# IsoPowerSupply.net
KiCad netlist of a schematic drawn in Altium Designer
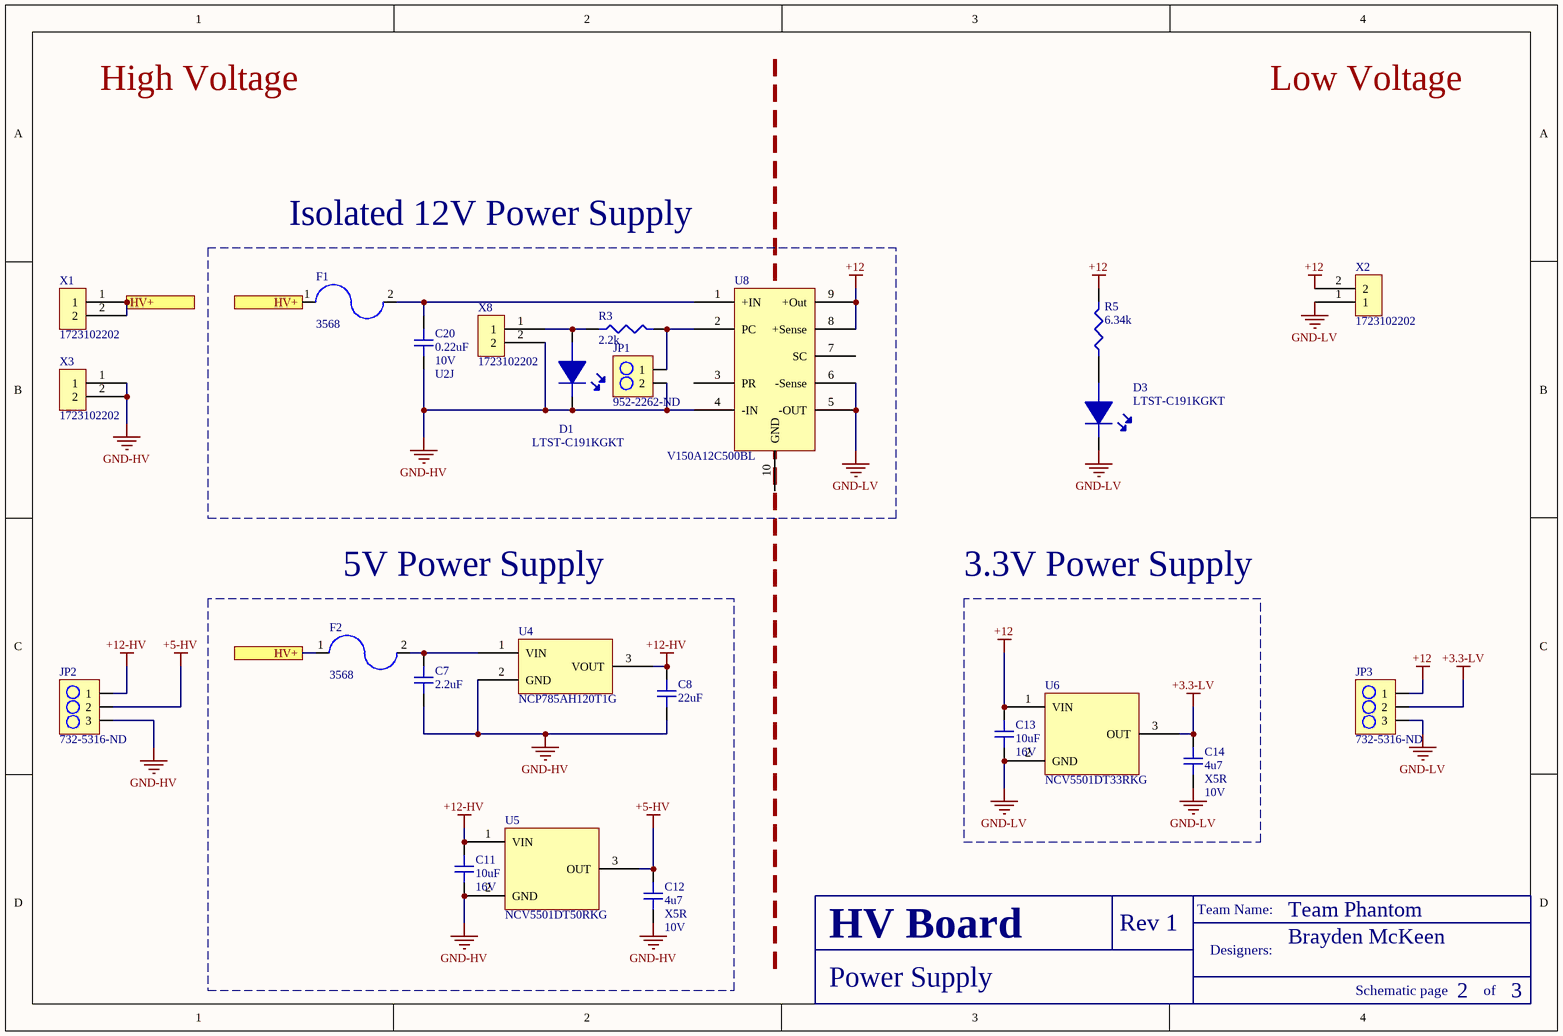
[diagram p0: IsoPowerSupply.SchDoc]

(export (version "E")
  (design (tool "Eeschema 10.0.6"))
  (components
    (comp (ref "C7")
      (value "2.2uF")
      (footprint "Cap-2.2u- ECW-FD2W225J4")
      (description "CAP FILM 2.2UF 5% 450VDC RADIAL")
      (fields
        (field (name "MANUFACTURER") "Panasonic")
        (field (name "MANUFACURER PART NUMBER") "ECW-FD2W225J4")
      )
      (libsource (lib "PHANTOM_LIBRARY") (part "ECW-FD2W225J4"))
    )
    (comp (ref "C8")
      (value "22uF")
      (footprint "C1206")
      (description "CAP CER 22UF 16V X7R 1210")
      (fields
        (field (name "MANUFACTURER") "Murata")
        (field (name "MANUFACTURER PART NUMBER") "GCM31CR71A226KE02L")
      )
      (libsource (lib "PHANTOM_LIBRARY") (part "GCM32ER71C226KE19L"))
    )
    (comp (ref "C11")
      (value "10uF")
      (footprint "PHANTOM_FOOTPRINTS:C0805")
      (description "CAP CER 10UF 16V X7R 0805")
      (fields
        (field (name "MANUFACTURER") "Samsung")
        (field (name "TOLERANCE") "10%")
        (field (name "VOLTAGE RATING") "16V")
      )
      (libsource (lib "PHANTOM_LIBRARY") (part "CL21B106KOQNNNG"))
    )
    (comp (ref "C12")
      (value "4u7")
      (footprint "C0805")
      (fields
        (field (name "MANUFACTURER") "Murata")
        (field (name "MANUFACTURER PART NUMBER") "GRM219R61A475KE34D")
        (field (name "TOLERANCE") "10%")
        (field (name "DIELECTRIC") "X5R")
        (field (name "VOLTAGE") "10V")
      )
      (libsource (lib "PHANTOM_LIBRARY") (part "GRM219R61A475KE34D"))
    )
    (comp (ref "C13")
      (value "10uF")
      (footprint "PHANTOM_FOOTPRINTS:C0805")
      (description "CAP CER 10UF 16V X7R 0805")
      (fields
        (field (name "MANUFACTURER") "Samsung")
        (field (name "TOLERANCE") "10%")
        (field (name "VOLTAGE RATING") "16V")
      )
      (libsource (lib "PHANTOM_LIBRARY") (part "CL21B106KOQNNNG"))
    )
    (comp (ref "C14")
      (value "4u7")
      (footprint "C0805")
      (fields
        (field (name "MANUFACTURER") "Murata")
        (field (name "MANUFACTURER PART NUMBER") "GRM219R61A475KE34D")
        (field (name "TOLERANCE") "10%")
        (field (name "DIELECTRIC") "X5R")
        (field (name "VOLTAGE") "10V")
      )
      (libsource (lib "PHANTOM_LIBRARY") (part "GRM219R61A475KE34D"))
    )
    (comp (ref "C20")
      (value "0.22uF")
      (footprint "Cap-0.22-SK057C224KAR")
      (description "CAP CER 0.22UF 500V X7R RADIAL")
      (fields
        (field (name "MANUFACTURER") "AVX Corporation")
        (field (name "MANUFACTURER PART NUMBER") "SK057C224KAR")
        (field (name "VOLTAGE RATING") "10V")
        (field (name "DIELECTRIC") "U2J")
      )
      (libsource (lib "PHANTOM_LIBRARY") (part "SK057C224KAR"))
    )
    (comp (ref "D1")
      (value "LTST-C191KGKT")
      (footprint "LED_0603")
      (description "LED GREEN CLEAR 0603 SMD")
      (fields (field (name "MANUFACTURER") "Vishay Lite-On"))
      (libsource (lib "PHANTOM_LIBRARY") (part "LTST-C191KGKT"))
    )
    (comp (ref "D3")
      (value "LTST-C191KGKT")
      (footprint "LED_0603")
      (description "LED GREEN CLEAR 0603 SMD")
      (fields (field (name "MANUFACTURER") "Vishay Lite-On"))
      (libsource (lib "PHANTOM_LIBRARY") (part "LTST-C191KGKT"))
    )
    (comp (ref "F1")
      (value "3568")
      (footprint "FUSE_MINI_HOLDER")
      (description "FUSE HOLDER MINI AUTO PC")
      (fields (field (name "MANUFACTURER") "Keystone Electronics") (field (name "VOLTAGE") "500V"))
      (libsource (lib "PHANTOM_LIBRARY") (part "3568"))
    )
    (comp (ref "F2")
      (value "3568")
      (footprint "FUSE_MINI_HOLDER")
      (description "FUSE HOLDER MINI AUTO PC")
      (fields (field (name "MANUFACTURER") "Keystone Electronics") (field (name "VOLTAGE") "500V"))
      (libsource (lib "PHANTOM_LIBRARY") (part "3568"))
    )
    (comp (ref "JP1")
      (value "952-2262-ND")
      (footprint "2PIN_HEADER")
      (description "CONN_HeaderPins2pos Headers & Wire Housings 02 SIL VERTICAL PIN HEADER TIN")
      (fields (field (name "MANUFACTURER") "Harwin") (field (name "MANUFACTURER PART NUMBER") "M20-9990246"))
      (libsource (lib "PHANTOM_LIBRARY") (part "M20-9990246"))
    )
    (comp (ref "JP2")
      (value "732-5316-ND")
      (footprint "3PIN_HEADER")
      (fields
        (field (name "MANUFACTURER") "Wurth Electronics")
        (field (name "MANUFACTURER PART NUMBER") "61300311121")
      )
      (libsource (lib "PHANTOM_LIBRARY") (part "61300311121"))
    )
    (comp (ref "JP3")
      (value "732-5316-ND")
      (footprint "3PIN_HEADER")
      (fields
        (field (name "MANUFACTURER") "Wurth Electronics")
        (field (name "MANUFACTURER PART NUMBER") "61300311121")
      )
      (libsource (lib "PHANTOM_LIBRARY") (part "61300311121"))
    )
    (comp (ref "R3")
      (value "2.2k")
      (footprint "R0805")
      (description "RES SMD 2.2K OHM 5% 1/8W")
      (fields
        (field (name "MANUFACTURER") "Yageo")
        (field (name "MANUFACTURER PART NUMBER") "RC0805JR-072K2L")
      )
      (libsource (lib "PHANTOM_LIBRARY") (part "RC0805JR-072K2L"))
    )
    (comp (ref "R5")
      (value "6.34k")
      (footprint "R0805")
      (description "RES SMD 6.34K OHM 1% 1/8W 0805")
      (fields
        (field (name "MANUFACTURER") "Panasonic")
        (field (name "MANUFACTURER PART NUMBER") "ERJ-6ENF6341V")
      )
      (libsource (lib "PHANTOM_LIBRARY") (part "ERJ-6ENF6341V"))
    )
    (comp (ref "U4")
      (value "NCP785AH120T1G")
      (footprint "NCP785AH120T1G")
      (description "IC REG LINEAR 12V 10MA SOT89-3")
      (fields (field (name "MANUFACTURER") "On Semiconductor"))
      (libsource (lib "PHANTOM_LIBRARY") (part "NCP785AH120T1G"))
    )
    (comp (ref "U5")
      (value "NCV5501DT50RKG")
      (footprint "NCV5501DT50RKG")
      (description "IC REG LINEAR 5V 500MA DPAK")
      (fields
        (field (name "MANUFACTURER") "On Semiconductor")
        (field (name "MANUFACTURER PART NUMBER") "NCP785AH120T1G")
      )
      (libsource (lib "PHANTOM_LIBRARY") (part "NCV5501DT50RKG"))
    )
    (comp (ref "U6")
      (value "NCV5501DT33RKG")
      (footprint "NCV5501DT50RKG")
      (description "IC REG LINEAR 3.3V 500MA DPAK")
      (fields (field (name "MANUFACTURER") "On Semiconductor"))
      (libsource (lib "PHANTOM_LIBRARY") (part "NCV5501DT33RKG"))
    )
    (comp (ref "U8")
      (value "V150A12C500BL")
      (footprint "Vicor-V150A12C500BL")
      (description "Isolated DC/DC Converters C 100/200/150 12v/ 41.7A")
      (fields
        (field (name "MANUFACTURER") "On Semiconductor")
        (field (name "MANUFACTURER PART NUMBER") "NCP785AH120T1G")
      )
      (libsource (lib "PHANTOM_LIBRARY") (part "V150A12C500BL"))
    )
    (comp (ref "X1")
      (value "1723102202")
      (footprint "Molex2Pin")
      (description "CONN HEADER R/A 2POS 3.5MM")
      (fields (field (name "MANUFACTURER") "Molex"))
      (libsource (lib "PHANTOM_LIBRARY") (part "1723102202"))
    )
    (comp (ref "X2")
      (value "1723102202")
      (footprint "Molex2Pin")
      (description "CONN HEADER R/A 2POS 3.5MM")
      (fields (field (name "MANUFACTURER") "Molex"))
      (libsource (lib "") (part "1723102202_1"))
    )
    (comp (ref "X3")
      (value "1723102202")
      (footprint "Molex2Pin")
      (description "CONN HEADER R/A 2POS 3.5MM")
      (fields (field (name "MANUFACTURER") "Molex"))
      (libsource (lib "PHANTOM_LIBRARY") (part "1723102202"))
    )
    (comp (ref "X8")
      (value "1723102202")
      (footprint "Molex2Pin")
      (description "CONN HEADER R/A 2POS 3.5MM")
      (fields (field (name "MANUFACTURER") "Molex"))
      (libsource (lib "PHANTOM_LIBRARY") (part "1723102202"))
    )
  )
  (nets
    (net (code "1") (name "+3.3-LV") (class "Default")
      (node (ref "C14") (pin "2") (pinfunction "2_2") (pintype "passive"))
      (node (ref "JP3") (pin "2") (pinfunction "2_2") (pintype "passive"))
      (node (ref "U6") (pin "3") (pinfunction "OUT_3") (pintype "passive"))
    )
    (net (code "2") (name "+5-HV") (class "Default")
      (node (ref "C12") (pin "2") (pinfunction "2_2") (pintype "passive"))
      (node (ref "JP2") (pin "2") (pinfunction "2_2") (pintype "passive"))
      (node (ref "U5") (pin "3") (pinfunction "OUT_3") (pintype "passive"))
    )
    (net (code "3") (name "+12") (class "Default")
      (node (ref "C13") (pin "2") (pinfunction "2_2") (pintype "passive"))
      (node (ref "JP3") (pin "1") (pinfunction "1_1") (pintype "passive"))
      (node (ref "R5") (pin "2") (pinfunction "2_2") (pintype "passive"))
      (node (ref "U6") (pin "1") (pinfunction "VIN_1") (pintype "passive"))
      (node (ref "U8") (pin "8") (pinfunction "+Sense_8") (pintype "passive"))
      (node (ref "U8") (pin "9") (pinfunction "+Out_9") (pintype "passive"))
      (node (ref "X2") (pin "2") (pinfunction "2_2") (pintype "passive"))
    )
    (net (code "4") (name "+12-HV") (class "Default")
      (node (ref "C11") (pin "2") (pinfunction "2_2") (pintype "passive"))
      (node (ref "C8") (pin "2") (pinfunction "2_2") (pintype "passive"))
      (node (ref "JP2") (pin "1") (pinfunction "1_1") (pintype "passive"))
      (node (ref "U4") (pin "3") (pinfunction "VOUT_3") (pintype "passive"))
      (node (ref "U5") (pin "1") (pinfunction "VIN_1") (pintype "passive"))
    )
    (net (code "5") (name "/HV+") (class "Default")
      (node (ref "F1") (pin "1") (pinfunction "1_1") (pintype "passive"))
      (node (ref "F2") (pin "1") (pinfunction "1_1") (pintype "passive"))
      (node (ref "X1") (pin "1") (pinfunction "1_1") (pintype "passive"))
      (node (ref "X1") (pin "2") (pinfunction "2_2") (pintype "passive"))
    )
    (net (code "6") (name "GND-HV") (class "Default")
      (node (ref "C11") (pin "1") (pinfunction "1_1") (pintype "passive"))
      (node (ref "C12") (pin "1") (pinfunction "1_1") (pintype "passive"))
      (node (ref "C20") (pin "1") (pinfunction "1_1") (pintype "passive"))
      (node (ref "C7") (pin "1") (pinfunction "1_1") (pintype "passive"))
      (node (ref "C8") (pin "1") (pinfunction "1_1") (pintype "passive"))
      (node (ref "D1") (pin "2") (pinfunction "2_2") (pintype "passive"))
      (node (ref "JP1") (pin "2") (pinfunction "2_2") (pintype "passive"))
      (node (ref "JP2") (pin "3") (pinfunction "3_3") (pintype "passive"))
      (node (ref "U4") (pin "2") (pinfunction "GND_2") (pintype "passive"))
      (node (ref "U5") (pin "2") (pinfunction "GND_2") (pintype "passive"))
      (node (ref "U8") (pin "4") (pinfunction "-IN_4") (pintype "passive"))
      (node (ref "X3") (pin "1") (pinfunction "1_1") (pintype "passive"))
      (node (ref "X3") (pin "2") (pinfunction "2_2") (pintype "passive"))
      (node (ref "X8") (pin "2") (pinfunction "2_2") (pintype "passive"))
    )
    (net (code "7") (name "GND-LV") (class "Default")
      (node (ref "C13") (pin "1") (pinfunction "1_1") (pintype "passive"))
      (node (ref "C14") (pin "1") (pinfunction "1_1") (pintype "passive"))
      (node (ref "D3") (pin "2") (pinfunction "2_2") (pintype "passive"))
      (node (ref "JP3") (pin "3") (pinfunction "3_3") (pintype "passive"))
      (node (ref "U6") (pin "2") (pinfunction "GND_2") (pintype "passive"))
      (node (ref "U8") (pin "5") (pinfunction "-OUT_5") (pintype "passive"))
      (node (ref "U8") (pin "6") (pinfunction "-Sense_6") (pintype "passive"))
      (node (ref "X2") (pin "1") (pinfunction "1_1") (pintype "passive"))
    )
    (net (code "8") (name "Net-(D1-Pad1)") (class "Default")
      (node (ref "D1") (pin "1") (pinfunction "1_1") (pintype "passive"))
      (node (ref "R3") (pin "1") (pinfunction "1_1") (pintype "passive"))
      (node (ref "X8") (pin "1") (pinfunction "1_1") (pintype "passive"))
    )
    (net (code "9") (name "Net-(D3-Pad1)") (class "Default")
      (node (ref "D3") (pin "1") (pinfunction "1_1") (pintype "passive"))
      (node (ref "R5") (pin "1") (pinfunction "1_1") (pintype "passive"))
    )
    (net (code "10") (name "Net-(U4-VIN)") (class "Default")
      (node (ref "C7") (pin "2") (pinfunction "2_2") (pintype "passive"))
      (node (ref "F2") (pin "2") (pinfunction "2_2") (pintype "passive"))
      (node (ref "U4") (pin "1") (pinfunction "VIN_1") (pintype "passive"))
    )
    (net (code "11") (name "Net-(U8-+IN)") (class "Default")
      (node (ref "C20") (pin "2") (pinfunction "2_2") (pintype "passive"))
      (node (ref "F1") (pin "2") (pinfunction "2_2") (pintype "passive"))
      (node (ref "U8") (pin "1") (pinfunction "+IN_1") (pintype "passive"))
    )
    (net (code "12") (name "Net-(U8-PC)") (class "Default")
      (node (ref "JP1") (pin "1") (pinfunction "1_1") (pintype "passive"))
      (node (ref "R3") (pin "2") (pinfunction "2_2") (pintype "passive"))
      (node (ref "U8") (pin "2") (pinfunction "PC_2") (pintype "passive"))
    )
    (net (code "13") (name "unconnected-(U8-GND-Pad10)") (class "Default")
      (node (ref "U8") (pin "10") (pinfunction "GND_10") (pintype "passive"))
    )
    (net (code "14") (name "unconnected-(U8-PR-Pad3)") (class "Default")
      (node (ref "U8") (pin "3") (pinfunction "PR_3") (pintype "passive"))
    )
    (net (code "15") (name "unconnected-(U8-SC-Pad7)") (class "Default")
      (node (ref "U8") (pin "7") (pinfunction "SC_7") (pintype "passive"))
    )
  )
)
